# Buffer.net
KiCad netlist of a schematic drawn in Altium Designer
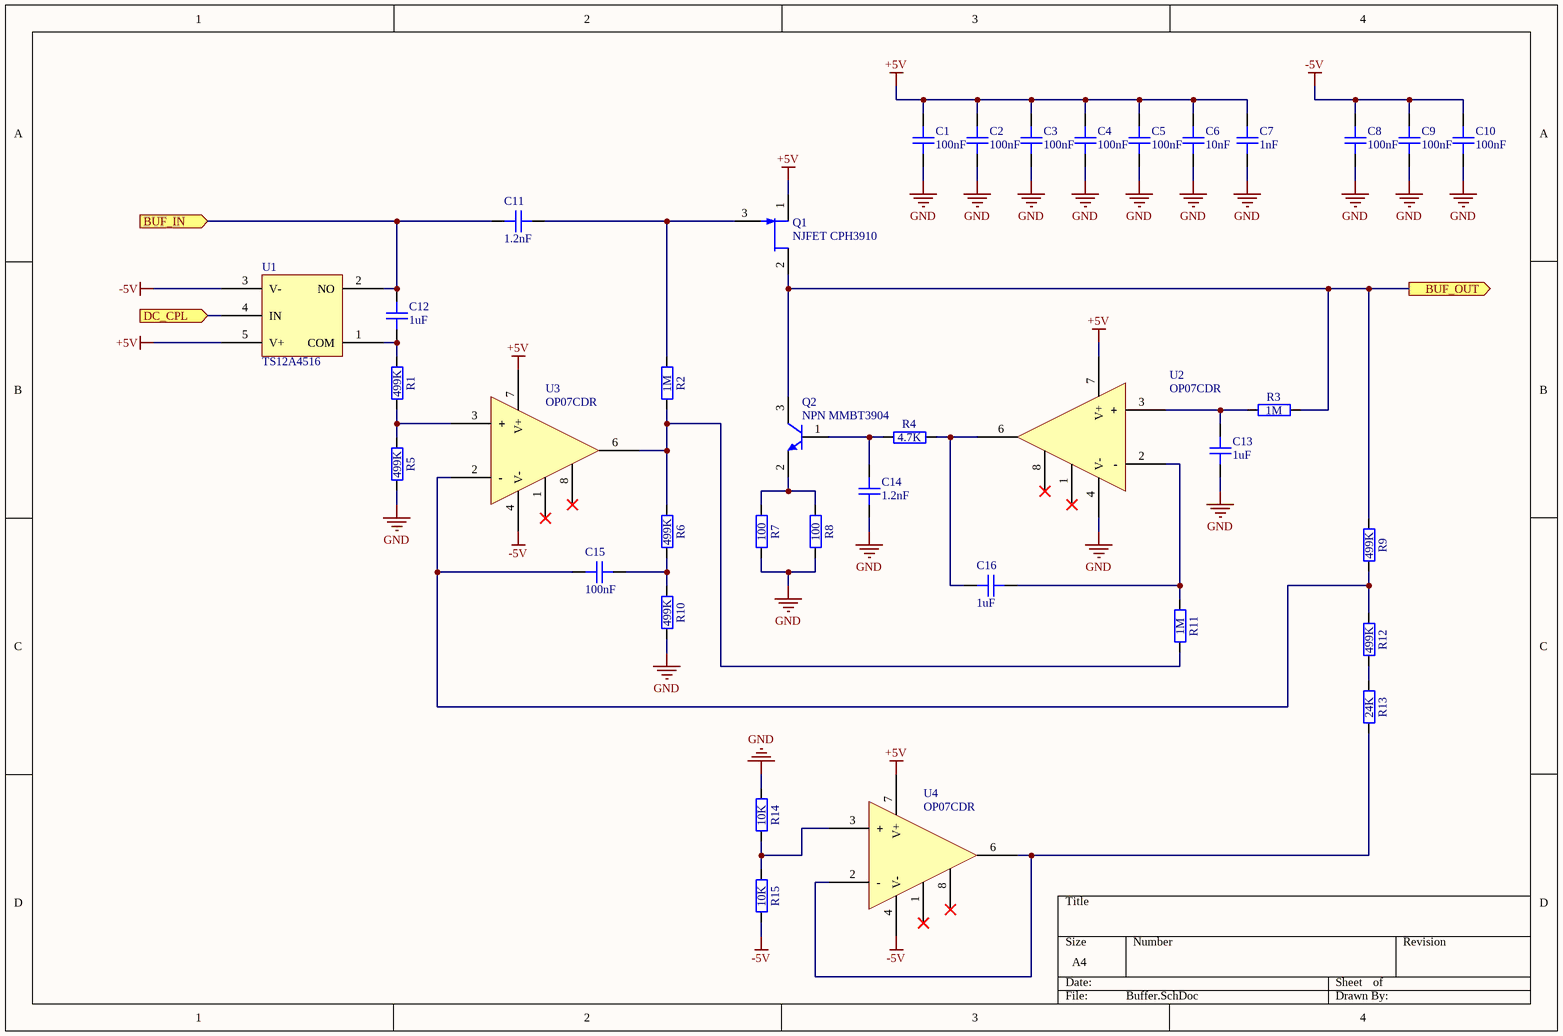
[diagram p0: Buffer.SchDoc]

(export (version "E")
  (design (tool "Eeschema 10.0.6"))
  (components
    (comp (ref "C1")
      (value "100nF")
      (footprint "GEN_C_0402")
      (fields (field (name "Comment") "CAP 100nF 16V X7R 0402"))
      (libsource (lib "DSO") (part "CAP 100nF 16V X7R 0402"))
    )
    (comp (ref "C2")
      (value "100nF")
      (footprint "GEN_C_0402")
      (fields (field (name "Comment") "CAP 100nF 16V X7R 0402"))
      (libsource (lib "DSO") (part "CAP 100nF 16V X7R 0402"))
    )
    (comp (ref "C3")
      (value "100nF")
      (footprint "GEN_C_0402")
      (fields (field (name "Comment") "CAP 100nF 16V X7R 0402"))
      (libsource (lib "DSO") (part "CAP 100nF 16V X7R 0402"))
    )
    (comp (ref "C4")
      (value "100nF")
      (footprint "GEN_C_0402")
      (fields (field (name "Comment") "CAP 100nF 16V X7R 0402"))
      (libsource (lib "DSO") (part "CAP 100nF 16V X7R 0402"))
    )
    (comp (ref "C5")
      (value "100nF")
      (footprint "GEN_C_0402")
      (fields (field (name "Comment") "CAP 100nF 16V X7R 0402"))
      (libsource (lib "DSO") (part "CAP 100nF 16V X7R 0402"))
    )
    (comp (ref "C6")
      (value "10nF")
      (footprint "GEN_C_0402")
      (fields (field (name "Comment") "CAP 10nF 50V X7R 0402"))
      (libsource (lib "DSO") (part "CAP 10nF 50V X7R 0402"))
    )
    (comp (ref "C7")
      (value "1nF")
      (footprint "GEN_C_0402")
      (fields (field (name "Comment") "CAP 1nF 50V X7R 0402"))
      (libsource (lib "DSO") (part "CAP 1nF 50V X7R 0402"))
    )
    (comp (ref "C8")
      (value "100nF")
      (footprint "GEN_C_0402")
      (fields (field (name "Comment") "CAP 100nF 16V X7R 0402"))
      (libsource (lib "DSO") (part "CAP 100nF 16V X7R 0402"))
    )
    (comp (ref "C9")
      (value "100nF")
      (footprint "GEN_C_0402")
      (fields (field (name "Comment") "CAP 100nF 16V X7R 0402"))
      (libsource (lib "DSO") (part "CAP 100nF 16V X7R 0402"))
    )
    (comp (ref "C10")
      (value "100nF")
      (footprint "GEN_C_0402")
      (fields (field (name "Comment") "CAP 100nF 16V X7R 0402"))
      (libsource (lib "DSO") (part "CAP 100nF 16V X7R 0402"))
    )
    (comp (ref "C11")
      (value "1.2nF")
      (footprint "GEN_C_0603")
      (libsource (lib "DSO") (part "CAP 1.2nF 50V C0G 0603"))
    )
    (comp (ref "C12")
      (value "1uF")
      (footprint "GEN_C_0402")
      (fields (field (name "Comment") "CAP 1uF 25V X5R 0402"))
      (libsource (lib "DSO") (part "CAP 1uF 25V X5R 0402"))
    )
    (comp (ref "C13")
      (value "1uF")
      (footprint "GEN_C_0402")
      (fields (field (name "Comment") "CAP 1uF 25V X5R 0402"))
      (libsource (lib "DSO") (part "CAP 1uF 25V X5R 0402"))
    )
    (comp (ref "C14")
      (value "1.2nF")
      (footprint "GEN_C_0603")
      (libsource (lib "DSO") (part "CAP 1.2nF 50V C0G 0603"))
    )
    (comp (ref "C15")
      (value "100nF")
      (footprint "GEN_C_0402")
      (fields (field (name "Comment") "CAP 100nF 16V X7R 0402"))
      (libsource (lib "DSO") (part "CAP 100nF 16V X7R 0402"))
    )
    (comp (ref "C16")
      (value "1uF")
      (footprint "GEN_C_0402")
      (fields (field (name "Comment") "CAP 1uF 25V X5R 0402"))
      (libsource (lib "DSO") (part "CAP 1uF 25V X5R 0402"))
    )
    (comp (ref "Q1")
      (value "NJFET CPH3910")
      (footprint "ON_SOT23_CPH3")
      (libsource (lib "DSO") (part "NJFET CPH3910"))
    )
    (comp (ref "Q2")
      (value "NPN MMBT3904")
      (footprint "MMC_SOT23")
      (libsource (lib "DSO") (part "NPN MMBT3904"))
    )
    (comp (ref "R1")
      (value "499K")
      (footprint "GEN_R_0402")
      (fields (field (name "TOLERANCE") "1%") (field (name "Comment") "RES 499K OHM 1% 1/10W 0402"))
      (libsource (lib "DSO") (part "RES 499K OHM 1% 1/10W 0402"))
    )
    (comp (ref "R2")
      (value "1M")
      (footprint "GEN_R_0402")
      (fields (field (name "TOLERANCE") "1%") (field (name "Comment") "RES 1M OHM 1% 1/10W 0402"))
      (libsource (lib "DSO") (part "RES 1M OHM 1% 1/10W 0402"))
    )
    (comp (ref "R3")
      (value "1M")
      (footprint "GEN_R_0402")
      (fields (field (name "TOLERANCE") "1%") (field (name "Comment") "RES 1M OHM 1% 1/10W 0402"))
      (libsource (lib "") (part "RES 1M OHM 1% 1/10W 0402_1"))
    )
    (comp (ref "R4")
      (value "4.7K")
      (footprint "GEN_R_0402")
      (fields (field (name "TOLERANCE") "1%") (field (name "Comment") "RES 4.7K OHM 1% 1/10W 0402"))
      (libsource (lib "DSO") (part "RES 4.7K OHM 1% 1/10W 0402"))
    )
    (comp (ref "R5")
      (value "499K")
      (footprint "GEN_R_0402")
      (fields (field (name "TOLERANCE") "1%") (field (name "Comment") "RES 499K OHM 1% 1/10W 0402"))
      (libsource (lib "DSO") (part "RES 499K OHM 1% 1/10W 0402"))
    )
    (comp (ref "R6")
      (value "499K")
      (footprint "GEN_R_0402")
      (fields (field (name "TOLERANCE") "1%") (field (name "Comment") "RES 499K OHM 1% 1/10W 0402"))
      (libsource (lib "DSO") (part "RES 499K OHM 1% 1/10W 0402"))
    )
    (comp (ref "R7")
      (value "100")
      (footprint "GEN_R_0402")
      (fields (field (name "TOLERANCE") "1%") (field (name "Comment") "RES 100 OHM 1% 1/10W 0402"))
      (libsource (lib "DSO") (part "RES 100 OHM 1% 1/10W 0402"))
    )
    (comp (ref "R8")
      (value "100")
      (footprint "GEN_R_0402")
      (fields (field (name "TOLERANCE") "1%") (field (name "Comment") "RES 100 OHM 1% 1/10W 0402"))
      (libsource (lib "DSO") (part "RES 100 OHM 1% 1/10W 0402"))
    )
    (comp (ref "R9")
      (value "499K")
      (footprint "GEN_R_0402")
      (fields (field (name "TOLERANCE") "1%") (field (name "Comment") "RES 499K OHM 1% 1/10W 0402"))
      (libsource (lib "DSO") (part "RES 499K OHM 1% 1/10W 0402"))
    )
    (comp (ref "R10")
      (value "499K")
      (footprint "GEN_R_0402")
      (fields (field (name "TOLERANCE") "1%") (field (name "Comment") "RES 499K OHM 1% 1/10W 0402"))
      (libsource (lib "DSO") (part "RES 499K OHM 1% 1/10W 0402"))
    )
    (comp (ref "R11")
      (value "1M")
      (footprint "GEN_R_0402")
      (fields (field (name "TOLERANCE") "1%") (field (name "Comment") "RES 1M OHM 1% 1/10W 0402"))
      (libsource (lib "DSO") (part "RES 1M OHM 1% 1/10W 0402"))
    )
    (comp (ref "R12")
      (value "499K")
      (footprint "GEN_R_0402")
      (fields (field (name "TOLERANCE") "1%") (field (name "Comment") "RES 499K OHM 1% 1/10W 0402"))
      (libsource (lib "DSO") (part "RES 499K OHM 1% 1/10W 0402"))
    )
    (comp (ref "R13")
      (value "24K")
      (footprint "GEN_R_0402")
      (fields (field (name "TOLERANCE") "1%") (field (name "Comment") "RES 24K OHM 1% 1/10W 0402"))
      (libsource (lib "DSO") (part "RES 24K OHM 1% 1/10W 0402"))
    )
    (comp (ref "R14")
      (value "10K")
      (footprint "GEN_R_0402")
      (fields (field (name "TOLERANCE") "1%") (field (name "Comment") "RES 10K OHM 1% 1/10W 0402"))
      (libsource (lib "DSO") (part "RES 10K OHM 1% 1/10W 0402"))
    )
    (comp (ref "R15")
      (value "10K")
      (footprint "GEN_R_0402")
      (fields (field (name "TOLERANCE") "1%") (field (name "Comment") "RES 10K OHM 1% 1/10W 0402"))
      (libsource (lib "DSO") (part "RES 10K OHM 1% 1/10W 0402"))
    )
    (comp (ref "U1")
      (value "TS12A4516")
      (footprint "GEN_SOT23_5_950_2900X1600X1450")
      (libsource (lib "DSO") (part "IC SWITCH SPST TS12A4516DBVR"))
    )
    (comp (ref "U2")
      (value "OP07CDR")
      (footprint "TI_SOIC8_D0008A")
      (libsource (lib "DSO") (part "IC OPAMP OP07CDR"))
    )
    (comp (ref "U3")
      (value "OP07CDR")
      (footprint "TI_SOIC8_D0008A")
      (libsource (lib "DSO") (part "IC OPAMP OP07CDR"))
    )
    (comp (ref "U4")
      (value "OP07CDR")
      (footprint "TI_SOIC8_D0008A")
      (libsource (lib "DSO") (part "IC OPAMP OP07CDR"))
    )
  )
  (nets
    (net (code "1") (name "+5V") (class "Default")
      (node (ref "C1") (pin "1") (pinfunction "1_1") (pintype "passive"))
      (node (ref "C2") (pin "1") (pinfunction "1_1") (pintype "passive"))
      (node (ref "C3") (pin "1") (pinfunction "1_1") (pintype "passive"))
      (node (ref "C4") (pin "1") (pinfunction "1_1") (pintype "passive"))
      (node (ref "C5") (pin "1") (pinfunction "1_1") (pintype "passive"))
      (node (ref "C6") (pin "2") (pinfunction "2_2") (pintype "passive"))
      (node (ref "C7") (pin "2") (pinfunction "2_2") (pintype "passive"))
      (node (ref "Q1") (pin "1") (pinfunction "S_1") (pintype "passive"))
      (node (ref "U1") (pin "5") (pinfunction "V+_5") (pintype "passive"))
      (node (ref "U2") (pin "7") (pinfunction "V+_7") (pintype "passive"))
      (node (ref "U3") (pin "7") (pinfunction "V+_7") (pintype "passive"))
      (node (ref "U4") (pin "7") (pinfunction "V+_7") (pintype "passive"))
    )
    (net (code "2") (name "-5V") (class "Default")
      (node (ref "C10") (pin "1") (pinfunction "1_1") (pintype "passive"))
      (node (ref "C8") (pin "1") (pinfunction "1_1") (pintype "passive"))
      (node (ref "C9") (pin "1") (pinfunction "1_1") (pintype "passive"))
      (node (ref "R15") (pin "1") (pinfunction "1_1") (pintype "passive"))
      (node (ref "U1") (pin "3") (pinfunction "V-_3") (pintype "passive"))
      (node (ref "U3") (pin "4") (pinfunction "V-_4") (pintype "passive"))
      (node (ref "U4") (pin "4") (pinfunction "V-_4") (pintype "passive"))
    )
    (net (code "3") (name "/BUF_IN") (class "Default")
      (node (ref "C11") (pin "2") (pinfunction "2_2") (pintype "passive"))
      (node (ref "C12") (pin "2") (pinfunction "2_2") (pintype "passive"))
      (node (ref "U1") (pin "2") (pinfunction "NO_2") (pintype "passive"))
    )
    (net (code "4") (name "/BUF_OUT") (class "Default")
      (node (ref "Q1") (pin "2") (pinfunction "D_2") (pintype "passive"))
      (node (ref "Q2") (pin "3") (pinfunction "C_3") (pintype "passive"))
      (node (ref "R3") (pin "1") (pinfunction "1_1") (pintype "passive"))
      (node (ref "R9") (pin "2") (pinfunction "2_2") (pintype "passive"))
    )
    (net (code "5") (name "/DC_CPL") (class "Default")
      (node (ref "U1") (pin "4") (pinfunction "IN_4") (pintype "passive"))
    )
    (net (code "6") (name "GND") (class "Default")
      (node (ref "C1") (pin "2") (pinfunction "2_2") (pintype "passive"))
      (node (ref "C10") (pin "2") (pinfunction "2_2") (pintype "passive"))
      (node (ref "C13") (pin "1") (pinfunction "1_1") (pintype "passive"))
      (node (ref "C14") (pin "1") (pinfunction "1_1") (pintype "passive"))
      (node (ref "C2") (pin "2") (pinfunction "2_2") (pintype "passive"))
      (node (ref "C3") (pin "2") (pinfunction "2_2") (pintype "passive"))
      (node (ref "C4") (pin "2") (pinfunction "2_2") (pintype "passive"))
      (node (ref "C5") (pin "2") (pinfunction "2_2") (pintype "passive"))
      (node (ref "C6") (pin "1") (pinfunction "1_1") (pintype "passive"))
      (node (ref "C7") (pin "1") (pinfunction "1_1") (pintype "passive"))
      (node (ref "C8") (pin "2") (pinfunction "2_2") (pintype "passive"))
      (node (ref "C9") (pin "2") (pinfunction "2_2") (pintype "passive"))
      (node (ref "R10") (pin "1") (pinfunction "1_1") (pintype "passive"))
      (node (ref "R14") (pin "2") (pinfunction "2_2") (pintype "passive"))
      (node (ref "R5") (pin "1") (pinfunction "1_1") (pintype "passive"))
      (node (ref "R7") (pin "1") (pinfunction "1_1") (pintype "passive"))
      (node (ref "R8") (pin "1") (pinfunction "1_1") (pintype "passive"))
      (node (ref "U2") (pin "4") (pinfunction "V-_4") (pintype "passive"))
    )
    (net (code "7") (name "Net-(C15-Pad1)") (class "Default")
      (node (ref "C15") (pin "1") (pinfunction "1_1") (pintype "passive"))
      (node (ref "R10") (pin "2") (pinfunction "2_2") (pintype "passive"))
      (node (ref "R6") (pin "1") (pinfunction "1_1") (pintype "passive"))
    )
    (net (code "8") (name "Net-(Q1-G)") (class "Default")
      (node (ref "C11") (pin "1") (pinfunction "1_1") (pintype "passive"))
      (node (ref "Q1") (pin "3") (pinfunction "G_3") (pintype "passive"))
      (node (ref "R2") (pin "2") (pinfunction "2_2") (pintype "passive"))
    )
    (net (code "9") (name "Net-(Q2-B)") (class "Default")
      (node (ref "C14") (pin "2") (pinfunction "2_2") (pintype "passive"))
      (node (ref "Q2") (pin "1") (pinfunction "B_1") (pintype "passive"))
      (node (ref "R4") (pin "1") (pinfunction "1_1") (pintype "passive"))
    )
    (net (code "10") (name "Net-(Q2-E)") (class "Default")
      (node (ref "Q2") (pin "2") (pinfunction "E_2") (pintype "passive"))
      (node (ref "R7") (pin "2") (pinfunction "2_2") (pintype "passive"))
      (node (ref "R8") (pin "2") (pinfunction "2_2") (pintype "passive"))
    )
    (net (code "11") (name "Net-(R12-Pad1)") (class "Default")
      (node (ref "R12") (pin "1") (pinfunction "1_1") (pintype "passive"))
      (node (ref "R13") (pin "2") (pinfunction "2_2") (pintype "passive"))
    )
    (net (code "12") (name "Net-(U1-COM)") (class "Default")
      (node (ref "C12") (pin "1") (pinfunction "1_1") (pintype "passive"))
      (node (ref "R1") (pin "2") (pinfunction "2_2") (pintype "passive"))
      (node (ref "U1") (pin "1") (pinfunction "COM_1") (pintype "passive"))
    )
    (net (code "13") (name "Net-(U2-+)") (class "Default")
      (node (ref "C13") (pin "2") (pinfunction "2_2") (pintype "passive"))
      (node (ref "R3") (pin "2") (pinfunction "2_2") (pintype "passive"))
      (node (ref "U2") (pin "3") (pinfunction "+_3") (pintype "passive"))
    )
    (net (code "14") (name "Net-(U2--)") (class "Default")
      (node (ref "C16") (pin "1") (pinfunction "1_1") (pintype "passive"))
      (node (ref "R11") (pin "2") (pinfunction "2_2") (pintype "passive"))
      (node (ref "U2") (pin "2") (pinfunction "-_2") (pintype "passive"))
    )
    (net (code "15") (name "Net-(U2-OUT)") (class "Default")
      (node (ref "C16") (pin "2") (pinfunction "2_2") (pintype "passive"))
      (node (ref "R4") (pin "2") (pinfunction "2_2") (pintype "passive"))
      (node (ref "U2") (pin "6") (pinfunction "OUT_6") (pintype "passive"))
    )
    (net (code "16") (name "Net-(U3-+)") (class "Default")
      (node (ref "R1") (pin "1") (pinfunction "1_1") (pintype "passive"))
      (node (ref "R5") (pin "2") (pinfunction "2_2") (pintype "passive"))
      (node (ref "U3") (pin "3") (pinfunction "+_3") (pintype "passive"))
    )
    (net (code "17") (name "Net-(U3--)") (class "Default")
      (node (ref "C15") (pin "2") (pinfunction "2_2") (pintype "passive"))
      (node (ref "R12") (pin "2") (pinfunction "2_2") (pintype "passive"))
      (node (ref "R9") (pin "1") (pinfunction "1_1") (pintype "passive"))
      (node (ref "U3") (pin "2") (pinfunction "-_2") (pintype "passive"))
    )
    (net (code "18") (name "Net-(U3-OUT)") (class "Default")
      (node (ref "R11") (pin "1") (pinfunction "1_1") (pintype "passive"))
      (node (ref "R2") (pin "1") (pinfunction "1_1") (pintype "passive"))
      (node (ref "R6") (pin "2") (pinfunction "2_2") (pintype "passive"))
      (node (ref "U3") (pin "6") (pinfunction "OUT_6") (pintype "passive"))
    )
    (net (code "19") (name "Net-(U4-+)") (class "Default")
      (node (ref "R14") (pin "1") (pinfunction "1_1") (pintype "passive"))
      (node (ref "R15") (pin "2") (pinfunction "2_2") (pintype "passive"))
      (node (ref "U4") (pin "3") (pinfunction "+_3") (pintype "passive"))
    )
    (net (code "20") (name "Net-(U4--)") (class "Default")
      (node (ref "R13") (pin "1") (pinfunction "1_1") (pintype "passive"))
      (node (ref "U4") (pin "2") (pinfunction "-_2") (pintype "passive"))
      (node (ref "U4") (pin "6") (pinfunction "OUT_6") (pintype "passive"))
    )
    (net (code "21") (name "unconnected-(U2-N1-Pad1)") (class "Default")
      (node (ref "U2") (pin "1") (pinfunction "N1_1") (pintype "passive+no_connect"))
    )
    (net (code "22") (name "unconnected-(U2-N2-Pad8)") (class "Default")
      (node (ref "U2") (pin "8") (pinfunction "N2_8") (pintype "passive+no_connect"))
    )
    (net (code "23") (name "unconnected-(U3-N1-Pad1)") (class "Default")
      (node (ref "U3") (pin "1") (pinfunction "N1_1") (pintype "passive+no_connect"))
    )
    (net (code "24") (name "unconnected-(U3-N2-Pad8)") (class "Default")
      (node (ref "U3") (pin "8") (pinfunction "N2_8") (pintype "passive+no_connect"))
    )
    (net (code "25") (name "unconnected-(U4-N1-Pad1)") (class "Default")
      (node (ref "U4") (pin "1") (pinfunction "N1_1") (pintype "passive+no_connect"))
    )
    (net (code "26") (name "unconnected-(U4-N2-Pad8)") (class "Default")
      (node (ref "U4") (pin "8") (pinfunction "N2_8") (pintype "passive+no_connect"))
    )
  )
)
